# design1.net
KiCad netlist of a schematic drawn in EAGLE
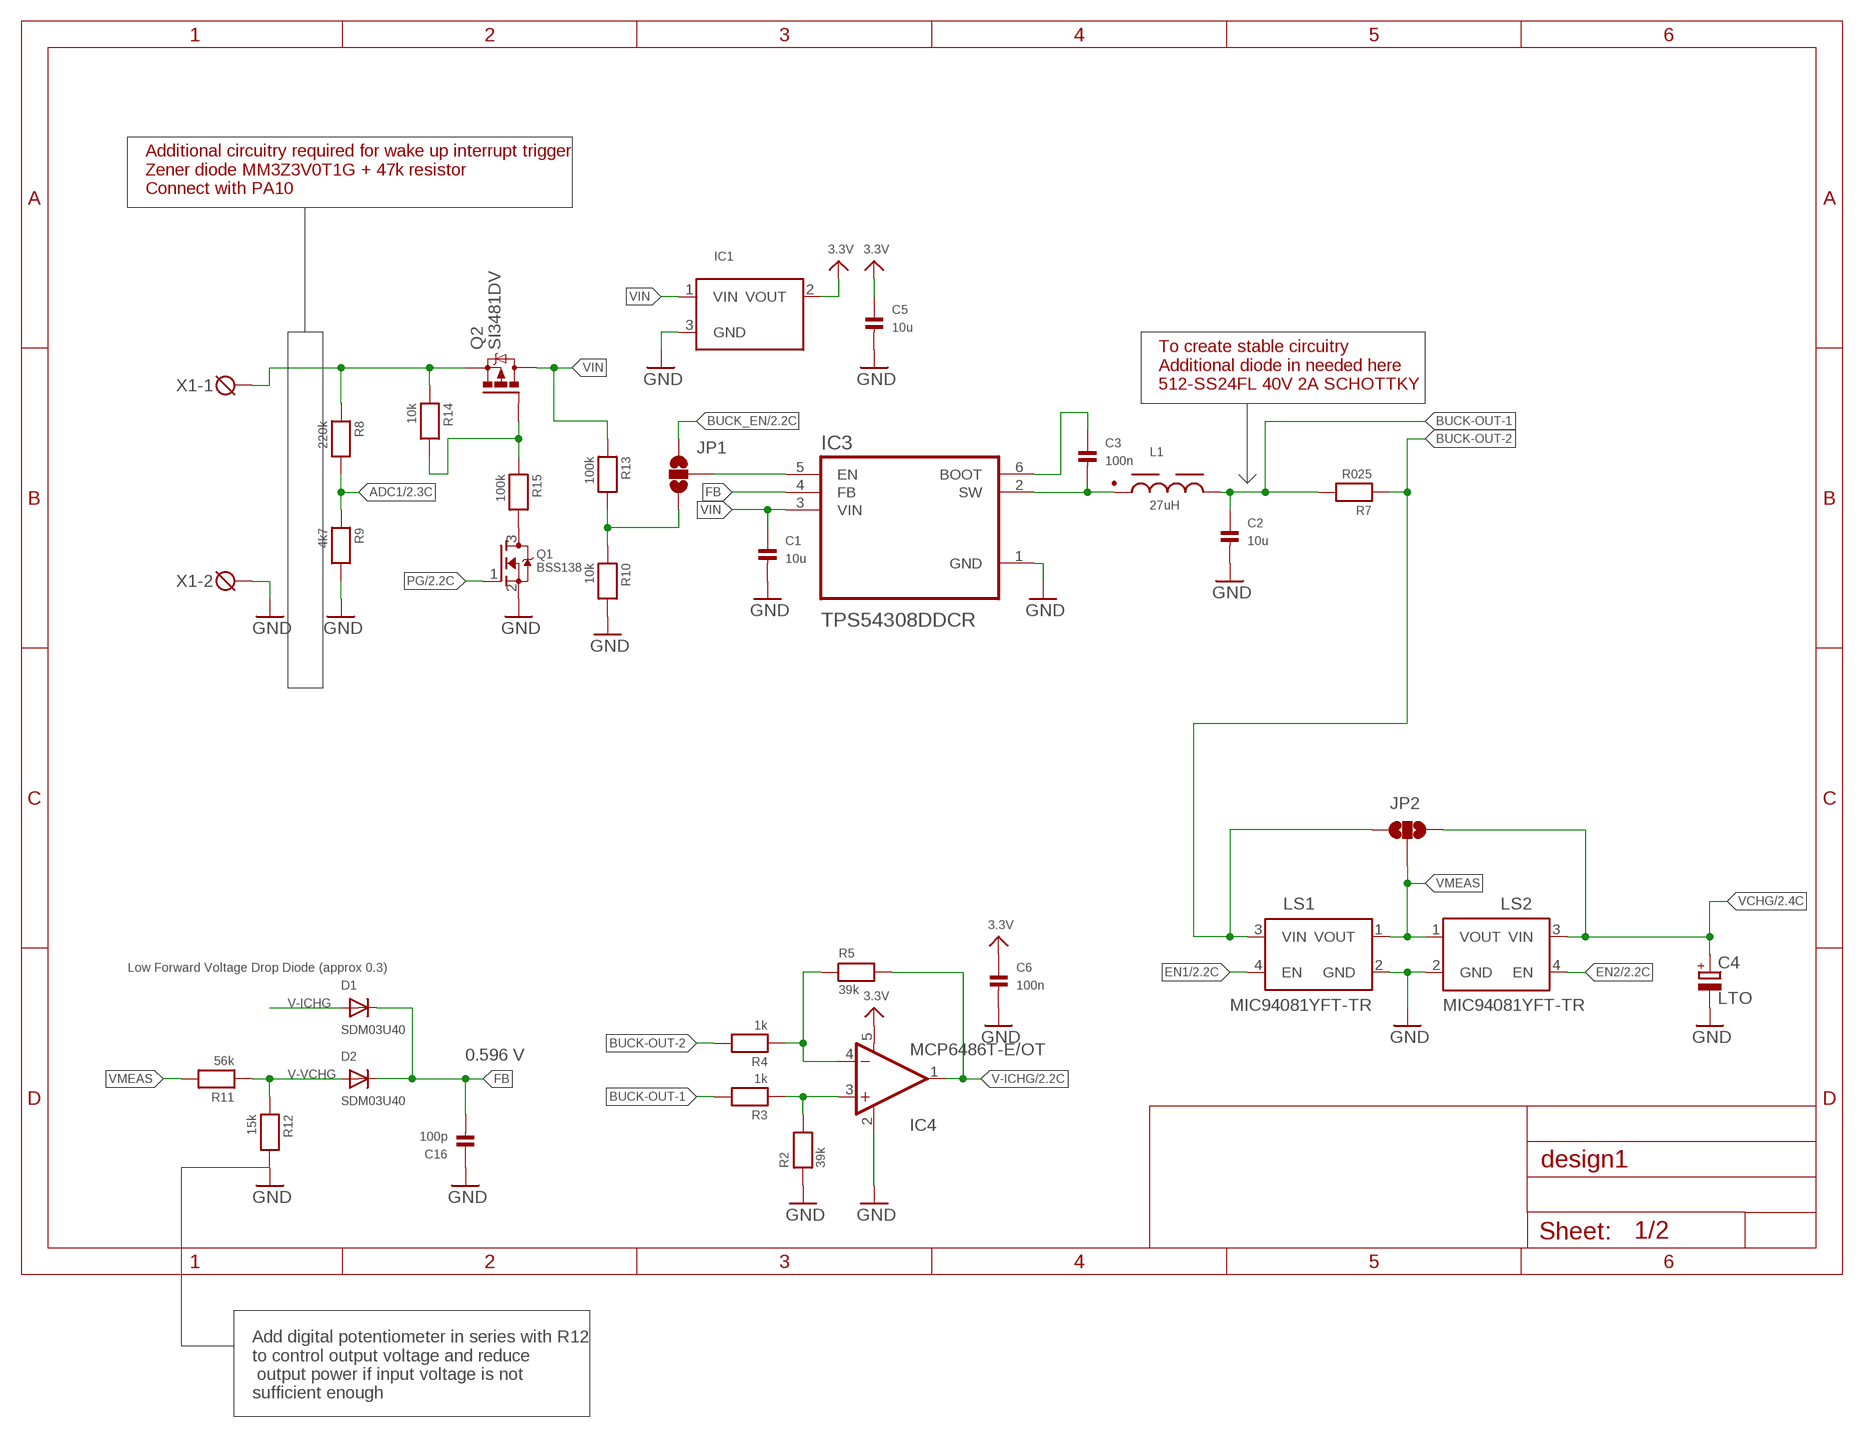
[diagram p0: schematic, sheet 1]
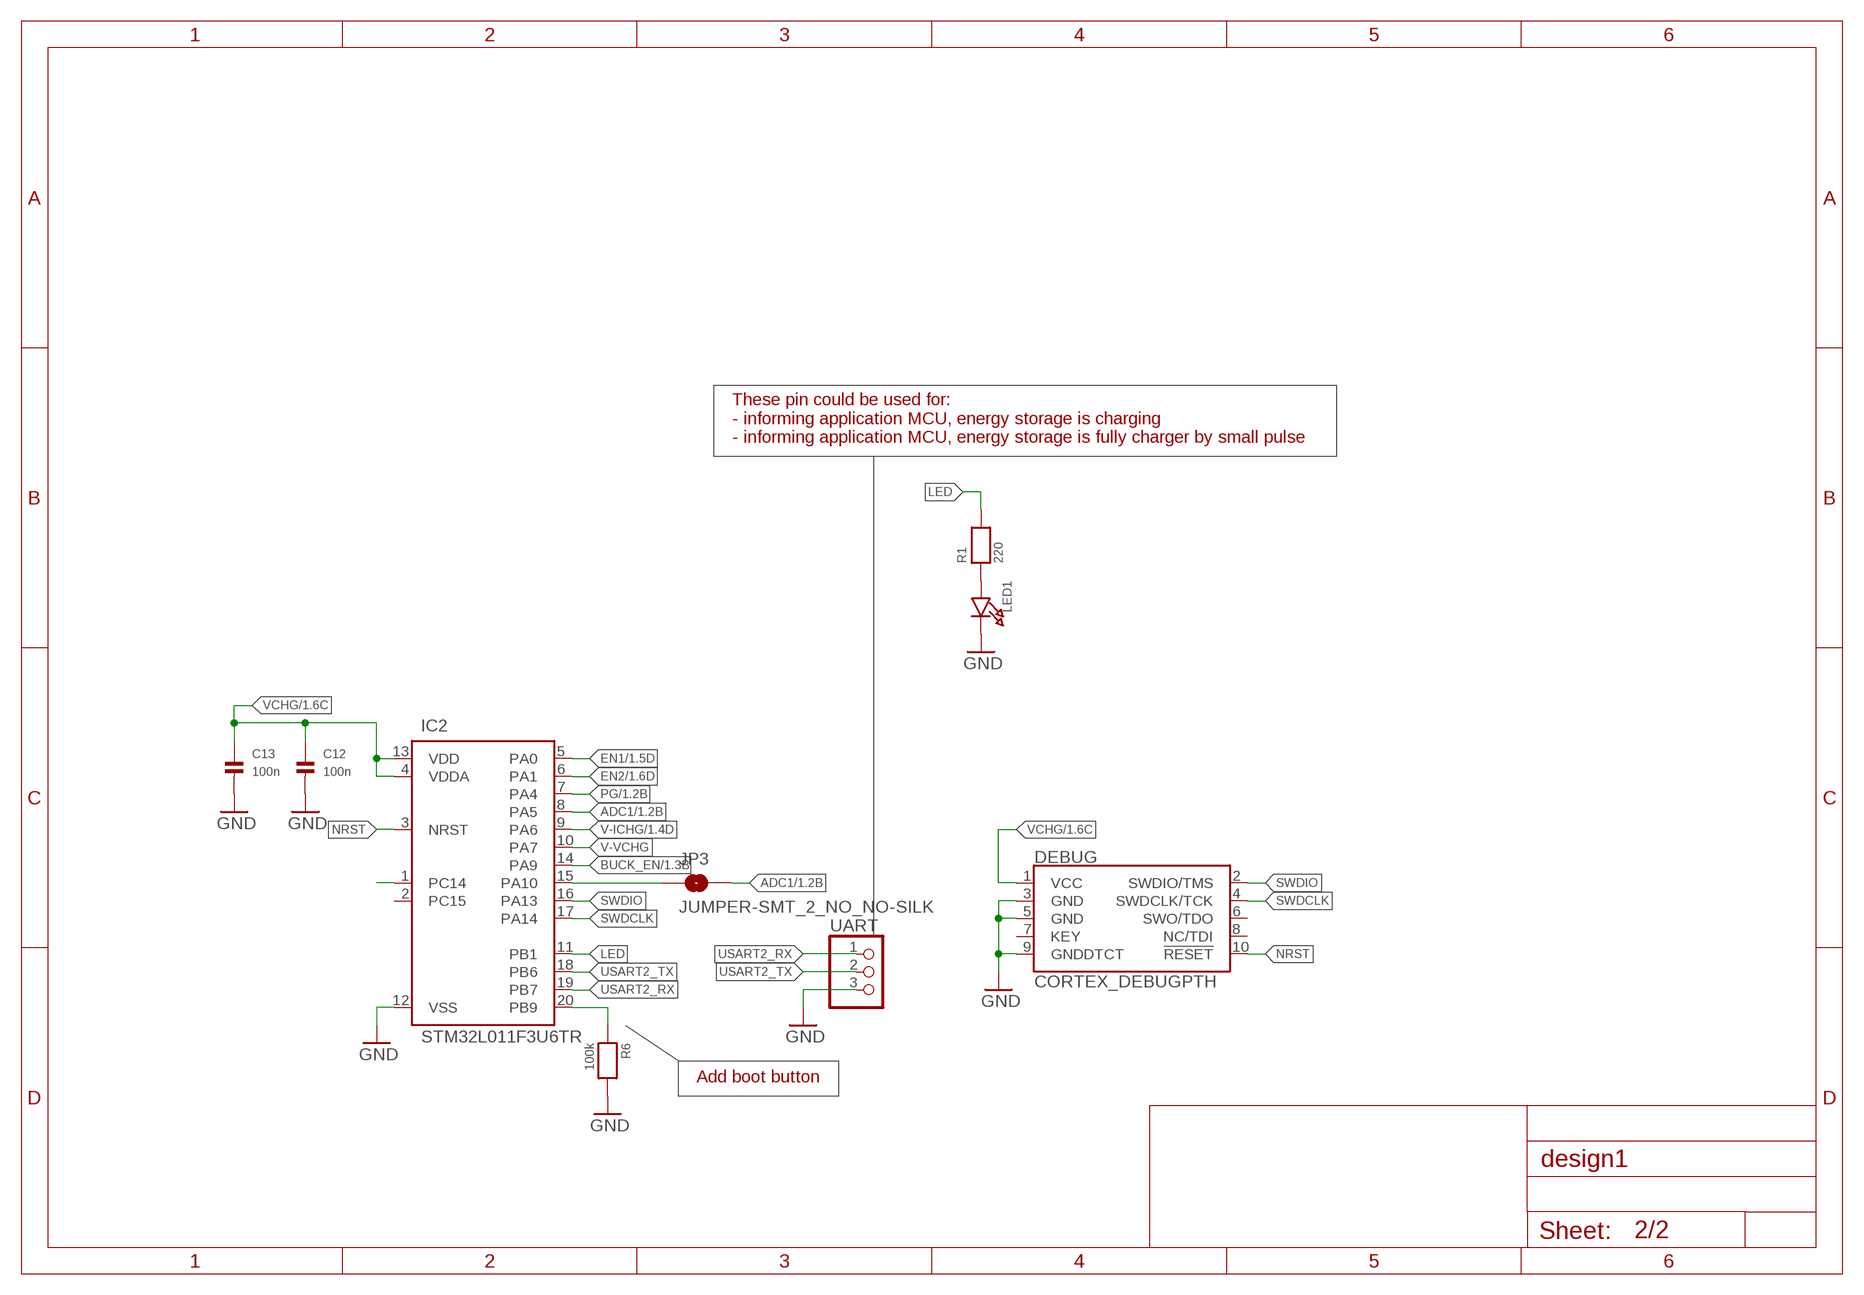
[diagram p1: schematic, sheet 2]

(export (version "E")
  (design (tool "Eeschema 10.0.6"))
  (components
    (comp (ref "C12")
      (value "100n")
      (footprint "eagle-import:0402")
      (libsource (lib "eagle-import") (part "CAP_CERAMIC0402"))
    )
    (comp (ref "C13")
      (value "100n")
      (footprint "eagle-import:0402")
      (libsource (lib "eagle-import") (part "CAP_CERAMIC0402"))
    )
    (comp (ref "DEBUG")
      (value "CORTEX_DEBUGPTH")
      (footprint "eagle-import:2X5-PTH-1.27MM")
      (libsource (lib "eagle-import") (part "CORTEX_DEBUGPTH"))
    )
    (comp (ref "IC2")
      (value "STM32L011F3U6TR")
      (footprint "eagle-import:QFN50P300X300X60-21N")
      (fields (field (name "MANUFACTURER") "STMicroelectronics"))
      (libsource (lib "eagle-import") (part "STM32L011F3U6TR"))
    )
    (comp (ref "JP3")
      (value "JUMPER-SMT_2_NO_NO-SILK")
      (footprint "eagle-import:SMT-JUMPER_2_NO_NO-SILK")
      (libsource (lib "eagle-import") (part "JUMPER-SMT_2_NO_NO-SILK"))
    )
    (comp (ref "LED1")
      (value "LED0805")
      (footprint "eagle-import:CHIPLED_0805")
      (libsource (lib "eagle-import") (part "LED0805"))
    )
    (comp (ref "R1")
      (value "220")
      (footprint "eagle-import:0603")
      (libsource (lib "eagle-import") (part "RESISTOR0603"))
    )
    (comp (ref "R6")
      (value "100k")
      (footprint "eagle-import:0603")
      (libsource (lib "eagle-import") (part "RESISTOR0603"))
    )
    (comp (ref "UART")
      (value "HEADER-1X3ROUND")
      (footprint "eagle-import:1X03_ROUND")
      (libsource (lib "eagle-import") (part "HEADER-1X3ROUND"))
    )
    (comp (ref "C1")
      (value "10u")
      (footprint "eagle-import:0603")
      (libsource (lib "eagle-import") (part "CAP_CERAMIC0603"))
    )
    (comp (ref "C2")
      (value "10u")
      (footprint "eagle-import:0603")
      (libsource (lib "eagle-import") (part "CAP_CERAMIC0603"))
    )
    (comp (ref "C3")
      (value "100n")
      (footprint "eagle-import:0603")
      (libsource (lib "eagle-import") (part "CAP_CERAMIC0603"))
    )
    (comp (ref "C4")
      (value "LTO")
      (footprint "eagle-import:E5-10,5")
      (libsource (lib "eagle-import") (part "CPOL-EUE5-10.5"))
    )
    (comp (ref "C5")
      (value "10u")
      (footprint "eagle-import:0603")
      (libsource (lib "eagle-import") (part "CAP_CERAMIC0603"))
    )
    (comp (ref "C6")
      (value "100n")
      (footprint "eagle-import:0402")
      (libsource (lib "eagle-import") (part "CAP_CERAMIC0402"))
    )
    (comp (ref "C16")
      (value "100p")
      (footprint "eagle-import:0603")
      (libsource (lib "eagle-import") (part "CAP_CERAMIC0603"))
    )
    (comp (ref "D1")
      (value "SDM03U40")
      (footprint "eagle-import:SOD-523")
      (libsource (lib "eagle-import") (part "DIODESOD-523"))
    )
    (comp (ref "D2")
      (value "SDM03U40")
      (footprint "eagle-import:SOD-523")
      (libsource (lib "eagle-import") (part "DIODESOD-523"))
    )
    (comp (ref "IC1")
      (value "VREG_SOT23")
      (footprint "eagle-import:SOT23-R")
      (libsource (lib "eagle-import") (part "VREG_SOT23"))
    )
    (comp (ref "IC3")
      (value "TPS54308DDCR")
      (footprint "eagle-import:SOT95P280X110-6N")
      (fields (field (name "MF") "Texas Instruments"))
      (libsource (lib "eagle-import") (part "TPS54308DDCR"))
    )
    (comp (ref "IC4")
      (value "MCP6486T-E/OT")
      (footprint "eagle-import:SOT23-5")
      (libsource (lib "eagle-import") (part "MCP6291T-E/OT"))
    )
    (comp (ref "JP1")
      (value "JUMPER-SMT_3_NO_NO-SILK")
      (footprint "eagle-import:SMT-JUMPER_3_NO_NO-SILK")
      (libsource (lib "eagle-import") (part "JUMPER-SMT_3_NO_NO-SILK"))
    )
    (comp (ref "JP2")
      (value "JUMPER-SMT_3_NO_NO-SILK")
      (footprint "eagle-import:SMT-JUMPER_3_NO_NO-SILK")
      (libsource (lib "eagle-import") (part "JUMPER-SMT_3_NO_NO-SILK"))
    )
    (comp (ref "L1")
      (value "27uH")
      (footprint "eagle-import:WE-PD_7332_7345_PLASTIC_BASE")
      (libsource (lib "eagle-import") (part "WE-PD_7332_PLASTIC_7447789127"))
    )
    (comp (ref "LS1")
      (value "MIC94081YFT-TR")
      (footprint "eagle-import:IC_MIC94081YFT-TR")
      (fields (field (name "MF") "Microchip"))
      (libsource (lib "eagle-import") (part "MIC94081YFT-TR"))
    )
    (comp (ref "LS2")
      (value "MIC94081YFT-TR")
      (footprint "eagle-import:IC_MIC94081YFT-TR")
      (fields (field (name "MF") "Microchip"))
      (libsource (lib "eagle-import") (part "MIC94081YFT-TR"))
    )
    (comp (ref "Q1")
      (value "BSS138")
      (footprint "eagle-import:SOT23-R")
      (libsource (lib "eagle-import") (part "MOSFET-NREFLOW"))
    )
    (comp (ref "Q2")
      (value "SI3481DV")
      (footprint "eagle-import:TSOP-6.PAC")
      (libsource (lib "eagle-import") (part "SI3481DV"))
    )
    (comp (ref "R2")
      (value "39k")
      (footprint "eagle-import:0603")
      (libsource (lib "eagle-import") (part "RESISTOR0603"))
    )
    (comp (ref "R3")
      (value "1k")
      (footprint "eagle-import:0603")
      (libsource (lib "eagle-import") (part "RESISTOR0603"))
    )
    (comp (ref "R4")
      (value "1k")
      (footprint "eagle-import:0603")
      (libsource (lib "eagle-import") (part "RESISTOR0603"))
    )
    (comp (ref "R5")
      (value "39k")
      (footprint "eagle-import:0603")
      (libsource (lib "eagle-import") (part "RESISTOR0603"))
    )
    (comp (ref "R7")
      (value "R025")
      (footprint "eagle-import:0603")
      (libsource (lib "eagle-import") (part "RESISTOR0603"))
    )
    (comp (ref "R8")
      (value "220k")
      (footprint "eagle-import:0603")
      (libsource (lib "eagle-import") (part "RESISTOR0603"))
    )
    (comp (ref "R9")
      (value "4k7")
      (footprint "eagle-import:0603")
      (libsource (lib "eagle-import") (part "RESISTOR0603"))
    )
    (comp (ref "R10")
      (value "10k")
      (footprint "eagle-import:0603")
      (libsource (lib "eagle-import") (part "RESISTOR0603"))
    )
    (comp (ref "R11")
      (value "56k")
      (footprint "eagle-import:0603")
      (libsource (lib "eagle-import") (part "RESISTOR0603"))
    )
    (comp (ref "R12")
      (value "15k")
      (footprint "eagle-import:0603")
      (libsource (lib "eagle-import") (part "RESISTOR0603"))
    )
    (comp (ref "R13")
      (value "100k")
      (footprint "eagle-import:0603")
      (libsource (lib "eagle-import") (part "RESISTOR0603"))
    )
    (comp (ref "R14")
      (value "10k")
      (footprint "eagle-import:0603")
      (libsource (lib "eagle-import") (part "RESISTOR0603"))
    )
    (comp (ref "R15")
      (value "100k")
      (footprint "eagle-import:0603")
      (libsource (lib "eagle-import") (part "RESISTOR0603"))
    )
    (comp (ref "X1")
      (value "DG3XX-02-5.0")
      (footprint "eagle-import:DG306-5.0-02P")
      (libsource (lib "eagle-import") (part "DG3XX-02-5.0"))
    )
  )
  (nets
    (net (code "1") (name "3.3V") (class "Default")
      (node (ref "C5") (pin "1") (pinfunction "P$1_1") (pintype "passive"))
      (node (ref "C6") (pin "1") (pinfunction "P$1_1") (pintype "passive"))
      (node (ref "IC1") (pin "2") (pinfunction "VOUT_2") (pintype "power_in"))
      (node (ref "IC4") (pin "5") (pinfunction "V+_5") (pintype "power_in"))
    )
    (net (code "2") (name "ADC1") (class "Default")
      (node (ref "IC2") (pin "8") (pinfunction "PA5_8") (pintype "bidirectional"))
      (node (ref "JP3") (pin "2") (pinfunction "2_2") (pintype "passive"))
      (node (ref "R8") (pin "2") (pinfunction "2_2") (pintype "passive"))
      (node (ref "R9") (pin "1") (pinfunction "1_1") (pintype "passive"))
    )
    (net (code "3") (name "BUCK-OUT-1") (class "Default")
      (node (ref "C2") (pin "1") (pinfunction "P$1_1") (pintype "passive"))
      (node (ref "L1") (pin "2") (pinfunction "2_2") (pintype "passive"))
      (node (ref "R3") (pin "2") (pinfunction "2_2") (pintype "passive"))
      (node (ref "R7") (pin "2") (pinfunction "2_2") (pintype "passive"))
    )
    (net (code "4") (name "BUCK-OUT-2") (class "Default")
      (node (ref "JP2") (pin "1") (pinfunction "1_1") (pintype "passive"))
      (node (ref "LS1") (pin "3") (pinfunction "VIN_3") (pintype "input"))
      (node (ref "R4") (pin "2") (pinfunction "2_2") (pintype "passive"))
      (node (ref "R7") (pin "1") (pinfunction "1_1") (pintype "passive"))
    )
    (net (code "5") (name "BUCK_EN") (class "Default")
      (node (ref "IC2") (pin "14") (pinfunction "PA9_14") (pintype "bidirectional"))
      (node (ref "JP1") (pin "3") (pinfunction "3_3") (pintype "passive"))
    )
    (net (code "6") (name "EN1") (class "Default")
      (node (ref "IC2") (pin "5") (pinfunction "PA0_5") (pintype "bidirectional"))
      (node (ref "LS1") (pin "4") (pinfunction "EN_4") (pintype "input"))
    )
    (net (code "7") (name "EN2") (class "Default")
      (node (ref "IC2") (pin "6") (pinfunction "PA1_6") (pintype "bidirectional"))
      (node (ref "LS2") (pin "4") (pinfunction "EN_4") (pintype "input"))
    )
    (net (code "8") (name "FB") (class "Default")
      (node (ref "C16") (pin "2") (pinfunction "P$2_2") (pintype "passive"))
      (node (ref "D1") (pin "K") (pinfunction "C_K") (pintype "passive"))
      (node (ref "D2") (pin "K") (pinfunction "C_K") (pintype "passive"))
      (node (ref "IC3") (pin "4") (pinfunction "FB_4") (pintype "input"))
    )
    (net (code "9") (name "GND") (class "Default")
      (node (ref "C1") (pin "2") (pinfunction "P$2_2") (pintype "passive"))
      (node (ref "C12") (pin "2") (pinfunction "P$2_2") (pintype "passive"))
      (node (ref "C13") (pin "2") (pinfunction "P$2_2") (pintype "passive"))
      (node (ref "C16") (pin "1") (pinfunction "P$1_1") (pintype "passive"))
      (node (ref "C2") (pin "2") (pinfunction "P$2_2") (pintype "passive"))
      (node (ref "C4") (pin "-") (pinfunction "-_-") (pintype "passive"))
      (node (ref "C5") (pin "2") (pinfunction "P$2_2") (pintype "passive"))
      (node (ref "C6") (pin "2") (pinfunction "P$2_2") (pintype "passive"))
      (node (ref "DEBUG") (pin "3") (pinfunction "GND_3") (pintype "bidirectional"))
      (node (ref "DEBUG") (pin "5") (pinfunction "GND_5") (pintype "bidirectional"))
      (node (ref "DEBUG") (pin "9") (pinfunction "GNDDTCT_9") (pintype "bidirectional"))
      (node (ref "IC1") (pin "3") (pinfunction "GND_3") (pintype "power_in"))
      (node (ref "IC2") (pin "12") (pinfunction "VSS_12") (pintype "bidirectional"))
      (node (ref "IC3") (pin "1") (pinfunction "GND_1") (pintype "power_in"))
      (node (ref "IC4") (pin "2") (pinfunction "V-_2") (pintype "power_in"))
      (node (ref "LED1") (pin "C") (pinfunction "C_C") (pintype "passive"))
      (node (ref "LS1") (pin "2") (pinfunction "GND_2") (pintype "power_in"))
      (node (ref "LS2") (pin "2") (pinfunction "GND_2") (pintype "power_in"))
      (node (ref "Q1") (pin "2") (pinfunction "S_2") (pintype "bidirectional"))
      (node (ref "R10") (pin "2") (pinfunction "2_2") (pintype "passive"))
      (node (ref "R12") (pin "2") (pinfunction "2_2") (pintype "passive"))
      (node (ref "R2") (pin "1") (pinfunction "1_1") (pintype "passive"))
      (node (ref "R6") (pin "2") (pinfunction "2_2") (pintype "passive"))
      (node (ref "R9") (pin "2") (pinfunction "2_2") (pintype "passive"))
      (node (ref "UART") (pin "3") (pinfunction "3_3") (pintype "passive"))
      (node (ref "X1") (pin "2") (pinfunction "KL_2") (pintype "passive"))
    )
    (net (code "10") (name "LED") (class "Default")
      (node (ref "IC2") (pin "11") (pinfunction "PB1_11") (pintype "bidirectional"))
      (node (ref "R1") (pin "2") (pinfunction "2_2") (pintype "passive"))
    )
    (net (code "11") (name "NRST") (class "Default")
      (node (ref "DEBUG") (pin "10") (pinfunction "~{RESET}_10") (pintype "bidirectional"))
      (node (ref "IC2") (pin "3") (pinfunction "NRST_3") (pintype "bidirectional"))
    )
    (net (code "12") (name "Net-(C3-P$1)") (class "Default")
      (node (ref "C3") (pin "1") (pinfunction "P$1_1") (pintype "passive"))
      (node (ref "IC3") (pin "6") (pinfunction "BOOT_6") (pintype "output"))
    )
    (net (code "13") (name "Net-(C3-P$2)") (class "Default")
      (node (ref "C3") (pin "2") (pinfunction "P$2_2") (pintype "passive"))
      (node (ref "IC3") (pin "2") (pinfunction "SW_2") (pintype "output"))
      (node (ref "L1") (pin "1") (pinfunction "1_1") (pintype "passive"))
    )
    (net (code "14") (name "Net-(IC2-PA10)") (class "Default")
      (node (ref "IC2") (pin "15") (pinfunction "PA10_15") (pintype "bidirectional"))
      (node (ref "JP3") (pin "1") (pinfunction "1_1") (pintype "passive"))
    )
    (net (code "15") (name "Net-(IC2-PB9)") (class "Default")
      (node (ref "IC2") (pin "20") (pinfunction "PB9_20") (pintype "bidirectional"))
      (node (ref "R6") (pin "1") (pinfunction "1_1") (pintype "passive"))
    )
    (net (code "16") (name "Net-(IC3-EN)") (class "Default")
      (node (ref "IC3") (pin "5") (pinfunction "EN_5") (pintype "input"))
      (node (ref "JP1") (pin "2") (pinfunction "2_2") (pintype "passive"))
    )
    (net (code "17") (name "Net-(IC4-+IN)") (class "Default")
      (node (ref "IC4") (pin "3") (pinfunction "+IN_3") (pintype "input"))
      (node (ref "R2") (pin "2") (pinfunction "2_2") (pintype "passive"))
      (node (ref "R3") (pin "1") (pinfunction "1_1") (pintype "passive"))
    )
    (net (code "18") (name "Net-(IC4--IN)") (class "Default")
      (node (ref "IC4") (pin "4") (pinfunction "-IN_4") (pintype "input"))
      (node (ref "R4") (pin "1") (pinfunction "1_1") (pintype "passive"))
      (node (ref "R5") (pin "1") (pinfunction "1_1") (pintype "passive"))
    )
    (net (code "19") (name "Net-(JP1-Pad1)") (class "Default")
      (node (ref "JP1") (pin "1") (pinfunction "1_1") (pintype "passive"))
      (node (ref "R10") (pin "1") (pinfunction "1_1") (pintype "passive"))
      (node (ref "R13") (pin "2") (pinfunction "2_2") (pintype "passive"))
    )
    (net (code "20") (name "Net-(LED1-PadA)") (class "Default")
      (node (ref "LED1") (pin "A") (pinfunction "A_A") (pintype "passive"))
      (node (ref "R1") (pin "1") (pinfunction "1_1") (pintype "passive"))
    )
    (net (code "21") (name "Net-(Q1-D)") (class "Default")
      (node (ref "Q1") (pin "3") (pinfunction "D_3") (pintype "bidirectional"))
      (node (ref "R15") (pin "2") (pinfunction "2_2") (pintype "passive"))
    )
    (net (code "22") (name "Net-(Q2-G)") (class "Default")
      (node (ref "Q2") (pin "3") (pinfunction "G_3") (pintype "passive"))
      (node (ref "R14") (pin "2") (pinfunction "2_2") (pintype "passive"))
      (node (ref "R15") (pin "1") (pinfunction "1_1") (pintype "passive"))
    )
    (net (code "23") (name "Net-(Q2-S)") (class "Default")
      (node (ref "Q2") (pin "4") (pinfunction "S_4") (pintype "passive"))
      (node (ref "R14") (pin "1") (pinfunction "1_1") (pintype "passive"))
      (node (ref "R8") (pin "1") (pinfunction "1_1") (pintype "passive"))
      (node (ref "X1") (pin "1") (pinfunction "KL_1") (pintype "passive"))
    )
    (net (code "24") (name "PG") (class "Default")
      (node (ref "IC2") (pin "7") (pinfunction "PA4_7") (pintype "bidirectional"))
      (node (ref "Q1") (pin "1") (pinfunction "G_1") (pintype "bidirectional"))
    )
    (net (code "25") (name "SWDCLK") (class "Default")
      (node (ref "DEBUG") (pin "4") (pinfunction "SWDCLK/TCK_4") (pintype "bidirectional"))
      (node (ref "IC2") (pin "17") (pinfunction "PA14_17") (pintype "bidirectional"))
    )
    (net (code "26") (name "SWDIO") (class "Default")
      (node (ref "DEBUG") (pin "2") (pinfunction "SWDIO/TMS_2") (pintype "bidirectional"))
      (node (ref "IC2") (pin "16") (pinfunction "PA13_16") (pintype "bidirectional"))
    )
    (net (code "27") (name "USART2_RX") (class "Default")
      (node (ref "IC2") (pin "19") (pinfunction "PB7_19") (pintype "bidirectional"))
      (node (ref "UART") (pin "1") (pinfunction "1_1") (pintype "passive"))
    )
    (net (code "28") (name "USART2_TX") (class "Default")
      (node (ref "IC2") (pin "18") (pinfunction "PB6_18") (pintype "bidirectional"))
      (node (ref "UART") (pin "2") (pinfunction "2_2") (pintype "passive"))
    )
    (net (code "29") (name "V-ICHG") (class "Default")
      (node (ref "D1") (pin "A") (pinfunction "A_A") (pintype "passive"))
      (node (ref "IC2") (pin "9") (pinfunction "PA6_9") (pintype "bidirectional"))
      (node (ref "IC4") (pin "1") (pinfunction "OUT_1") (pintype "output"))
      (node (ref "R5") (pin "2") (pinfunction "2_2") (pintype "passive"))
    )
    (net (code "30") (name "V-VCHG") (class "Default")
      (node (ref "D2") (pin "A") (pinfunction "A_A") (pintype "passive"))
      (node (ref "IC2") (pin "10") (pinfunction "PA7_10") (pintype "bidirectional"))
      (node (ref "R11") (pin "1") (pinfunction "1_1") (pintype "passive"))
      (node (ref "R12") (pin "1") (pinfunction "1_1") (pintype "passive"))
    )
    (net (code "31") (name "VCHG") (class "Default")
      (node (ref "C12") (pin "1") (pinfunction "P$1_1") (pintype "passive"))
      (node (ref "C13") (pin "1") (pinfunction "P$1_1") (pintype "passive"))
      (node (ref "C4") (pin "+") (pinfunction "+_+") (pintype "passive"))
      (node (ref "DEBUG") (pin "1") (pinfunction "VCC_1") (pintype "bidirectional"))
      (node (ref "IC2") (pin "13") (pinfunction "VDD_13") (pintype "bidirectional"))
      (node (ref "IC2") (pin "4") (pinfunction "VDDA_4") (pintype "bidirectional"))
      (node (ref "JP2") (pin "3") (pinfunction "3_3") (pintype "passive"))
      (node (ref "LS2") (pin "3") (pinfunction "VIN_3") (pintype "input"))
    )
    (net (code "32") (name "VIN") (class "Default")
      (node (ref "C1") (pin "1") (pinfunction "P$1_1") (pintype "passive"))
      (node (ref "IC1") (pin "1") (pinfunction "VIN_1") (pintype "power_in"))
      (node (ref "IC3") (pin "3") (pinfunction "VIN_3") (pintype "input"))
      (node (ref "Q2") (pin "1") (pinfunction "D_1") (pintype "passive"))
      (node (ref "Q2") (pin "2") (pinfunction "D_2") (pintype "passive"))
      (node (ref "Q2") (pin "5") (pinfunction "D_5") (pintype "passive"))
      (node (ref "Q2") (pin "6") (pinfunction "D_6") (pintype "passive"))
      (node (ref "R13") (pin "1") (pinfunction "1_1") (pintype "passive"))
    )
    (net (code "33") (name "VMEAS") (class "Default")
      (node (ref "JP2") (pin "2") (pinfunction "2_2") (pintype "passive"))
      (node (ref "LS1") (pin "1") (pinfunction "VOUT_1") (pintype "output"))
      (node (ref "LS2") (pin "1") (pinfunction "VOUT_1") (pintype "output"))
      (node (ref "R11") (pin "2") (pinfunction "2_2") (pintype "passive"))
    )
    (net (code "34") (name "unconnected-(DEBUG-KEY-Pad7)") (class "Default")
      (node (ref "DEBUG") (pin "7") (pinfunction "KEY_7") (pintype "bidirectional"))
    )
    (net (code "35") (name "unconnected-(DEBUG-NC{slash}TDI-Pad8)") (class "Default")
      (node (ref "DEBUG") (pin "8") (pinfunction "NC/TDI_8") (pintype "bidirectional"))
    )
    (net (code "36") (name "unconnected-(DEBUG-SWO{slash}TDO-Pad6)") (class "Default")
      (node (ref "DEBUG") (pin "6") (pinfunction "SWO/TDO_6") (pintype "bidirectional"))
    )
    (net (code "37") (name "unconnected-(IC2-PC14-Pad1)") (class "Default")
      (node (ref "IC2") (pin "1") (pinfunction "PC14_1") (pintype "bidirectional"))
    )
    (net (code "38") (name "unconnected-(IC2-PC15-Pad2)") (class "Default")
      (node (ref "IC2") (pin "2") (pinfunction "PC15_2") (pintype "bidirectional"))
    )
  )
)
